# 19V_Converter.net
KiCad netlist of a schematic drawn in Altium Designer
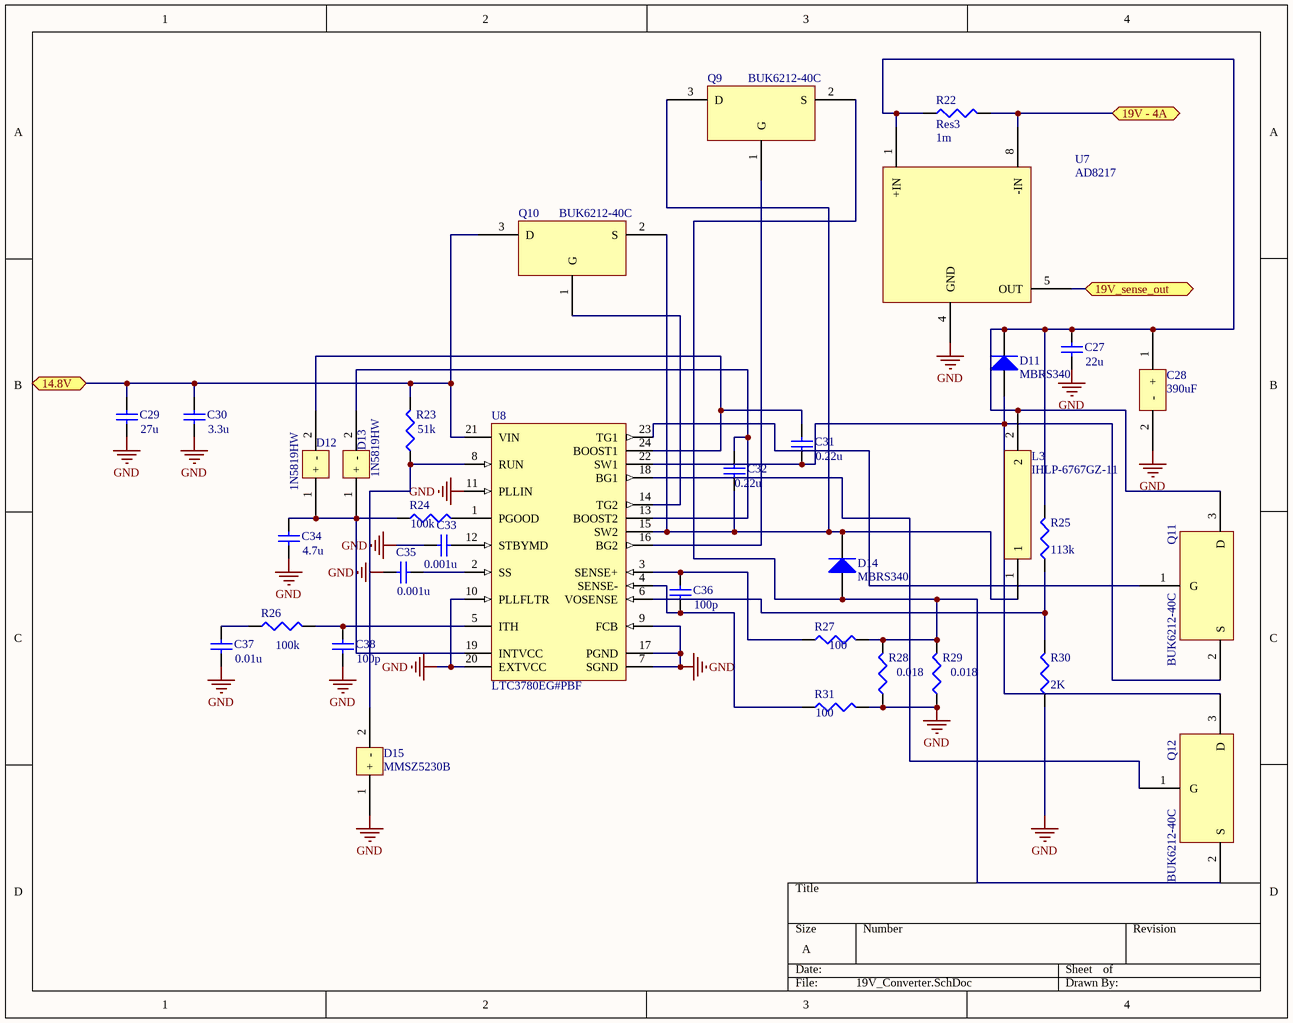
[diagram p0: 19V_Converter.SchDoc]

(export (version "E")
  (design (tool "Eeschema 10.0.6"))
  (components
    (comp (ref "C27")
      (value "22u")
      (footprint "C1206")
      (description "Capacitor (Semiconductor SIM Model)")
      (fields (field (name "Comment") "Cap Semi") (field (name "PUBLISHER") "Altium Limited"))
      (libsource (lib "Miscellaneous Devices") (part "Cap Semi"))
    )
    (comp (ref "C28")
      (value "390uF")
      (footprint "PCV1E391MCL2GS")
      (description "Aluminum Capacitor")
      (libsource (lib "Integrated_Library") (part "PCV1E391MCL2GS"))
    )
    (comp (ref "C29")
      (value "27u")
      (footprint "C1206")
      (description "Capacitor (Semiconductor SIM Model)")
      (fields (field (name "Comment") "Cap Semi") (field (name "PUBLISHER") "Altium Limited"))
      (libsource (lib "Miscellaneous Devices") (part "Cap Semi"))
    )
    (comp (ref "C30")
      (value "3.3u")
      (footprint "C1206")
      (description "Capacitor (Semiconductor SIM Model)")
      (fields (field (name "Comment") "Cap Semi") (field (name "PUBLISHER") "Altium Limited"))
      (libsource (lib "Miscellaneous Devices") (part "Cap Semi"))
    )
    (comp (ref "C31")
      (value "0.22u")
      (footprint "C1206")
      (description "Capacitor (Semiconductor SIM Model)")
      (fields (field (name "Comment") "Cap Semi") (field (name "PUBLISHER") "Altium Limited"))
      (libsource (lib "Miscellaneous Devices") (part "Cap Semi"))
    )
    (comp (ref "C32")
      (value "0.22u")
      (footprint "C1206")
      (description "Capacitor (Semiconductor SIM Model)")
      (fields (field (name "Comment") "Cap Semi") (field (name "PUBLISHER") "Altium Limited"))
      (libsource (lib "Miscellaneous Devices") (part "Cap Semi"))
    )
    (comp (ref "C33")
      (value "0.001u")
      (footprint "C1206")
      (description "Capacitor (Semiconductor SIM Model)")
      (fields (field (name "Comment") "Cap Semi") (field (name "PUBLISHER") "Altium Limited"))
      (libsource (lib "Miscellaneous Devices") (part "Cap Semi"))
    )
    (comp (ref "C34")
      (value "4.7u")
      (footprint "C1206")
      (description "Capacitor (Semiconductor SIM Model)")
      (fields (field (name "Comment") "Cap Semi") (field (name "PUBLISHER") "Altium Limited"))
      (libsource (lib "Miscellaneous Devices") (part "Cap Semi"))
    )
    (comp (ref "C35")
      (value "0.001u")
      (footprint "C1206")
      (description "Capacitor (Semiconductor SIM Model)")
      (fields (field (name "Comment") "Cap Semi") (field (name "PUBLISHER") "Altium Limited"))
      (libsource (lib "Miscellaneous Devices") (part "Cap Semi"))
    )
    (comp (ref "C36")
      (value "100p")
      (footprint "C1206")
      (description "Capacitor (Semiconductor SIM Model)")
      (fields (field (name "Comment") "Cap Semi") (field (name "PUBLISHER") "Altium Limited"))
      (libsource (lib "Miscellaneous Devices") (part "Cap Semi"))
    )
    (comp (ref "C37")
      (value "0.01u")
      (footprint "C1206")
      (description "Capacitor (Semiconductor SIM Model)")
      (fields (field (name "Comment") "Cap Semi") (field (name "PUBLISHER") "Altium Limited"))
      (libsource (lib "Miscellaneous Devices") (part "Cap Semi"))
    )
    (comp (ref "C38")
      (value "100p")
      (footprint "C1206")
      (description "Capacitor (Semiconductor SIM Model)")
      (fields (field (name "Comment") "Cap Semi") (field (name "PUBLISHER") "Altium Limited"))
      (libsource (lib "Miscellaneous Devices") (part "Cap Semi"))
    )
    (comp (ref "D11")
      (value "MBRS340")
      (footprint "SMC")
      (description "Default Diode")
      (fields (field (name "PUBLISHER") "Altium Limited"))
      (libsource (lib "Miscellaneous Devices") (part "Diode"))
    )
    (comp (ref "D12")
      (value "1N5819HW")
      (footprint "1N5819HW")
      (description "1A Schottky Barrier Rectifier")
      (libsource (lib "Integrated_Library") (part "1N5819HW"))
    )
    (comp (ref "D13")
      (value "1N5819HW")
      (footprint "1N5819HW")
      (description "1A Schottky Barrier Rectifier")
      (libsource (lib "Integrated_Library") (part "1N5819HW"))
    )
    (comp (ref "D14")
      (value "MBRS340")
      (footprint "SMC")
      (description "Default Diode")
      (fields (field (name "PUBLISHER") "Altium Limited"))
      (libsource (lib "Miscellaneous Devices") (part "Diode"))
    )
    (comp (ref "D15")
      (value "MMSZ5230B")
      (footprint "MMSZ5230B")
      (description "Zener Diode")
      (libsource (lib "Integrated_Library") (part "MMSZ5230B"))
    )
    (comp (ref "L3")
      (value "IHLP-6767GZ-11")
      (footprint "IHLP-6767GZ-11")
      (description "Inductor")
      (libsource (lib "Power_Board_Parts_Library_Final") (part "IHLP-6767GZ-11"))
    )
    (comp (ref "Q9")
      (value "BUK6212-40C")
      (footprint "BUK6212-40C")
      (description "N-Channel TrenchMOS Intermediate Level FET")
      (libsource (lib "") (part "BUK6212-40C_1"))
    )
    (comp (ref "Q10")
      (value "BUK6212-40C")
      (footprint "BUK6212-40C")
      (description "N-Channel TrenchMOS Intermediate Level FET")
      (libsource (lib "") (part "BUK6212-40C_1"))
    )
    (comp (ref "Q11")
      (value "BUK6212-40C")
      (footprint "BUK6212-40C")
      (description "N-Channel TrenchMOS Intermediate Level FET")
      (libsource (lib "Integrated_Library") (part "BUK6212-40C"))
    )
    (comp (ref "Q12")
      (value "BUK6212-40C")
      (footprint "BUK6212-40C")
      (description "N-Channel TrenchMOS Intermediate Level FET")
      (libsource (lib "Integrated_Library") (part "BUK6212-40C"))
    )
    (comp (ref "R22")
      (value "Res3")
      (footprint "14-1210")
      (description "Resistor")
      (fields (field (name "ALTIUM_VALUE") "1m") (field (name "PUBLISHER") "Altium Limited"))
      (libsource (lib "Miscellaneous Devices") (part "Res3"))
    )
    (comp (ref "R23")
      (value "51k")
      (footprint "J1-0603")
      (description "Resistor")
      (fields (field (name "Comment") "Res3") (field (name "PUBLISHER") "Altium Limited"))
      (libsource (lib "Miscellaneous Devices") (part "Res3"))
    )
    (comp (ref "R24")
      (value "100k")
      (footprint "J1-0603")
      (description "Resistor")
      (fields (field (name "Comment") "Res3") (field (name "PUBLISHER") "Altium Limited"))
      (libsource (lib "Miscellaneous Devices") (part "Res3"))
    )
    (comp (ref "R25")
      (value "113k")
      (footprint "J1-0603")
      (description "Resistor")
      (fields (field (name "Comment") "Res3") (field (name "PUBLISHER") "Altium Limited"))
      (libsource (lib "Miscellaneous Devices") (part "Res3"))
    )
    (comp (ref "R26")
      (value "100k")
      (footprint "J1-0603")
      (description "Resistor")
      (fields (field (name "Comment") "Res3") (field (name "PUBLISHER") "Altium Limited"))
      (libsource (lib "Miscellaneous Devices") (part "Res3"))
    )
    (comp (ref "R27")
      (value "100")
      (footprint "J1-0603")
      (description "Resistor")
      (fields (field (name "Comment") "Res3") (field (name "PUBLISHER") "Altium Limited"))
      (libsource (lib "Miscellaneous Devices") (part "Res3"))
    )
    (comp (ref "R28")
      (value "0.018")
      (footprint "J1-0603")
      (description "Resistor")
      (fields (field (name "Comment") "Res3") (field (name "PUBLISHER") "Altium Limited"))
      (libsource (lib "Miscellaneous Devices") (part "Res3"))
    )
    (comp (ref "R29")
      (value "0.018")
      (footprint "J1-0603")
      (description "Resistor")
      (fields (field (name "Comment") "Res3") (field (name "PUBLISHER") "Altium Limited"))
      (libsource (lib "Miscellaneous Devices") (part "Res3"))
    )
    (comp (ref "R30")
      (value "2K")
      (footprint "J1-0603")
      (description "Resistor")
      (fields (field (name "Comment") "Res3") (field (name "PUBLISHER") "Altium Limited"))
      (libsource (lib "Miscellaneous Devices") (part "Res3"))
    )
    (comp (ref "R31")
      (value "100")
      (footprint "J1-0603")
      (description "Resistor")
      (fields (field (name "Comment") "Res3") (field (name "PUBLISHER") "Altium Limited"))
      (libsource (lib "Miscellaneous Devices") (part "Res3"))
    )
    (comp (ref "U7")
      (value "AD8217")
      (footprint "AD8217")
      (description "Current Shunt Moniter")
      (libsource (lib "Integrated_Library") (part "AD8217"))
    )
    (comp (ref "U8")
      (value "LTC3780EG#PBF")
      (footprint "LTC3780 24-Leaqd Plastic SSOP")
      (fields (field (name "MANUFACTURER") "Linear Technology"))
      (libsource (lib "Integrated_Library") (part "LTC3780EG#PBF"))
    )
  )
  (nets
    (net (code "1") (name "/14.8V") (class "Default")
      (node (ref "C29") (pin "2") (pinfunction "2_2") (pintype "passive"))
      (node (ref "C30") (pin "2") (pinfunction "2_2") (pintype "passive"))
      (node (ref "Q10") (pin "3") (pinfunction "D_3") (pintype "passive"))
      (node (ref "R23") (pin "2") (pinfunction "2_2") (pintype "passive"))
      (node (ref "U8") (pin "21") (pinfunction "VIN_21") (pintype "power_in"))
    )
    (net (code "2") (name "/19V - 4A") (class "Default")
      (node (ref "R22") (pin "2") (pinfunction "2_2") (pintype "passive"))
      (node (ref "U7") (pin "8") (pinfunction "-IN_8") (pintype "passive"))
    )
    (net (code "3") (name "/19V_sense_out") (class "Default")
      (node (ref "U7") (pin "5") (pinfunction "OUT_5") (pintype "passive"))
    )
    (net (code "4") (name "GND") (class "Default")
      (node (ref "C27") (pin "1") (pinfunction "1_1") (pintype "passive"))
      (node (ref "C28") (pin "2") (pinfunction "-_2") (pintype "passive"))
      (node (ref "C29") (pin "1") (pinfunction "1_1") (pintype "passive"))
      (node (ref "C30") (pin "1") (pinfunction "1_1") (pintype "passive"))
      (node (ref "C33") (pin "1") (pinfunction "1_1") (pintype "passive"))
      (node (ref "C34") (pin "1") (pinfunction "1_1") (pintype "passive"))
      (node (ref "C35") (pin "1") (pinfunction "1_1") (pintype "passive"))
      (node (ref "C37") (pin "1") (pinfunction "1_1") (pintype "passive"))
      (node (ref "C38") (pin "1") (pinfunction "1_1") (pintype "passive"))
      (node (ref "D15") (pin "1") (pinfunction "+_1") (pintype "passive"))
      (node (ref "R28") (pin "1") (pinfunction "1_1") (pintype "passive"))
      (node (ref "R29") (pin "1") (pinfunction "1_1") (pintype "passive"))
      (node (ref "R30") (pin "1") (pinfunction "1_1") (pintype "passive"))
      (node (ref "R31") (pin "2") (pinfunction "2_2") (pintype "passive"))
      (node (ref "U7") (pin "4") (pinfunction "GND_4") (pintype "passive"))
      (node (ref "U8") (pin "10") (pinfunction "PLLFLTR_10") (pintype "input"))
      (node (ref "U8") (pin "11") (pinfunction "PLLIN_11") (pintype "input"))
      (node (ref "U8") (pin "17") (pinfunction "PGND_17") (pintype "power_in"))
      (node (ref "U8") (pin "20") (pinfunction "EXTVCC_20") (pintype "power_in"))
      (node (ref "U8") (pin "7") (pinfunction "SGND_7") (pintype "power_in"))
      (node (ref "U8") (pin "9") (pinfunction "FCB_9") (pintype "input"))
    )
    (net (code "5") (name "Net-(C28-+)") (class "Default")
      (node (ref "C27") (pin "2") (pinfunction "2_2") (pintype "passive"))
      (node (ref "C28") (pin "1") (pinfunction "+_1") (pintype "passive"))
      (node (ref "D11") (pin "2") (pinfunction "K_2") (pintype "passive"))
      (node (ref "L3") (pin "2") (pinfunction "2_2") (pintype "passive"))
      (node (ref "Q11") (pin "3") (pinfunction "D_3") (pintype "passive"))
      (node (ref "R22") (pin "1") (pinfunction "1_1") (pintype "passive"))
      (node (ref "R25") (pin "2") (pinfunction "2_2") (pintype "passive"))
      (node (ref "U7") (pin "1") (pinfunction "+IN_1") (pintype "passive"))
    )
    (net (code "6") (name "Net-(C37-Pad2)") (class "Default")
      (node (ref "C37") (pin "2") (pinfunction "2_2") (pintype "passive"))
      (node (ref "R26") (pin "1") (pinfunction "1_1") (pintype "passive"))
    )
    (net (code "7") (name "Net-(D11-A)") (class "Default")
      (node (ref "C31") (pin "1") (pinfunction "1_1") (pintype "passive"))
      (node (ref "D11") (pin "1") (pinfunction "A_1") (pintype "passive"))
      (node (ref "Q11") (pin "2") (pinfunction "S_2") (pintype "passive"))
      (node (ref "Q12") (pin "3") (pinfunction "D_3") (pintype "passive"))
      (node (ref "U8") (pin "22") (pinfunction "SW1_22") (pintype "passive"))
    )
    (net (code "8") (name "Net-(D12-+)") (class "Default")
      (node (ref "C34") (pin "2") (pinfunction "2_2") (pintype "passive"))
      (node (ref "D12") (pin "1") (pinfunction "+_1") (pintype "passive"))
      (node (ref "D13") (pin "1") (pinfunction "+_1") (pintype "passive"))
      (node (ref "R24") (pin "1") (pinfunction "1_1") (pintype "passive"))
      (node (ref "U8") (pin "19") (pinfunction "INTVCC_19") (pintype "power_in"))
    )
    (net (code "9") (name "Net-(D12--)") (class "Default")
      (node (ref "C31") (pin "2") (pinfunction "2_2") (pintype "passive"))
      (node (ref "D12") (pin "2") (pinfunction "-_2") (pintype "passive"))
      (node (ref "U8") (pin "24") (pinfunction "BOOST1_24") (pintype "passive"))
    )
    (net (code "10") (name "Net-(D13--)") (class "Default")
      (node (ref "C32") (pin "2") (pinfunction "2_2") (pintype "passive"))
      (node (ref "D13") (pin "2") (pinfunction "-_2") (pintype "passive"))
      (node (ref "U8") (pin "13") (pinfunction "BOOST2_13") (pintype "passive"))
    )
    (net (code "11") (name "Net-(D14-A)") (class "Default")
      (node (ref "D14") (pin "1") (pinfunction "A_1") (pintype "passive"))
      (node (ref "Q12") (pin "2") (pinfunction "S_2") (pintype "passive"))
      (node (ref "Q9") (pin "2") (pinfunction "S_2") (pintype "passive"))
      (node (ref "R27") (pin "2") (pinfunction "2_2") (pintype "passive"))
      (node (ref "R28") (pin "2") (pinfunction "2_2") (pintype "passive"))
      (node (ref "R29") (pin "2") (pinfunction "2_2") (pintype "passive"))
    )
    (net (code "12") (name "Net-(D14-K)") (class "Default")
      (node (ref "C32") (pin "1") (pinfunction "1_1") (pintype "passive"))
      (node (ref "D14") (pin "2") (pinfunction "K_2") (pintype "passive"))
      (node (ref "L3") (pin "1") (pinfunction "1_1") (pintype "passive"))
      (node (ref "Q10") (pin "2") (pinfunction "S_2") (pintype "passive"))
      (node (ref "Q9") (pin "3") (pinfunction "D_3") (pintype "passive"))
      (node (ref "U8") (pin "15") (pinfunction "SW2_15") (pintype "passive"))
    )
    (net (code "13") (name "Net-(D15--)") (class "Default")
      (node (ref "D15") (pin "2") (pinfunction "-_2") (pintype "passive"))
      (node (ref "R23") (pin "1") (pinfunction "1_1") (pintype "passive"))
      (node (ref "U8") (pin "8") (pinfunction "RUN_8") (pintype "input"))
    )
    (net (code "14") (name "Net-(Q9-G)") (class "Default")
      (node (ref "Q9") (pin "1") (pinfunction "G_1") (pintype "passive"))
      (node (ref "U8") (pin "16") (pinfunction "BG2_16") (pintype "output"))
    )
    (net (code "15") (name "Net-(Q10-G)") (class "Default")
      (node (ref "Q10") (pin "1") (pinfunction "G_1") (pintype "passive"))
      (node (ref "U8") (pin "14") (pinfunction "TG2_14") (pintype "output"))
    )
    (net (code "16") (name "Net-(Q11-G)") (class "Default")
      (node (ref "Q11") (pin "1") (pinfunction "G_1") (pintype "passive"))
      (node (ref "U8") (pin "23") (pinfunction "TG1_23") (pintype "output"))
    )
    (net (code "17") (name "Net-(Q12-G)") (class "Default")
      (node (ref "Q12") (pin "1") (pinfunction "G_1") (pintype "passive"))
      (node (ref "U8") (pin "18") (pinfunction "BG1_18") (pintype "output"))
    )
    (net (code "18") (name "Net-(U8-ITH)") (class "Default")
      (node (ref "C38") (pin "2") (pinfunction "2_2") (pintype "passive"))
      (node (ref "R26") (pin "2") (pinfunction "2_2") (pintype "passive"))
      (node (ref "U8") (pin "5") (pinfunction "ITH_5") (pintype "passive"))
    )
    (net (code "19") (name "Net-(U8-PGOOD)") (class "Default")
      (node (ref "R24") (pin "2") (pinfunction "2_2") (pintype "passive"))
      (node (ref "U8") (pin "1") (pinfunction "PGOOD_1") (pintype "open_collector"))
    )
    (net (code "20") (name "Net-(U8-SENSE+)") (class "Default")
      (node (ref "C36") (pin "2") (pinfunction "2_2") (pintype "passive"))
      (node (ref "R27") (pin "1") (pinfunction "1_1") (pintype "passive"))
      (node (ref "U8") (pin "3") (pinfunction "SENSE+_3") (pintype "input"))
    )
    (net (code "21") (name "Net-(U8-SENSE-)") (class "Default")
      (node (ref "C36") (pin "1") (pinfunction "1_1") (pintype "passive"))
      (node (ref "R31") (pin "1") (pinfunction "1_1") (pintype "passive"))
      (node (ref "U8") (pin "4") (pinfunction "SENSE-_4") (pintype "input"))
    )
    (net (code "22") (name "Net-(U8-SS)") (class "Default")
      (node (ref "C35") (pin "2") (pinfunction "2_2") (pintype "passive"))
      (node (ref "U8") (pin "2") (pinfunction "SS_2") (pintype "input"))
    )
    (net (code "23") (name "Net-(U8-STBYMD)") (class "Default")
      (node (ref "C33") (pin "2") (pinfunction "2_2") (pintype "passive"))
      (node (ref "U8") (pin "12") (pinfunction "STBYMD_12") (pintype "input"))
    )
    (net (code "24") (name "Net-(U8-VOSENSE)") (class "Default")
      (node (ref "R25") (pin "1") (pinfunction "1_1") (pintype "passive"))
      (node (ref "R30") (pin "2") (pinfunction "2_2") (pintype "passive"))
      (node (ref "U8") (pin "6") (pinfunction "VOSENSE_6") (pintype "input"))
    )
  )
)
